# Phoenix_FC_shield.net
KiCad netlist of a schematic drawn in EAGLE
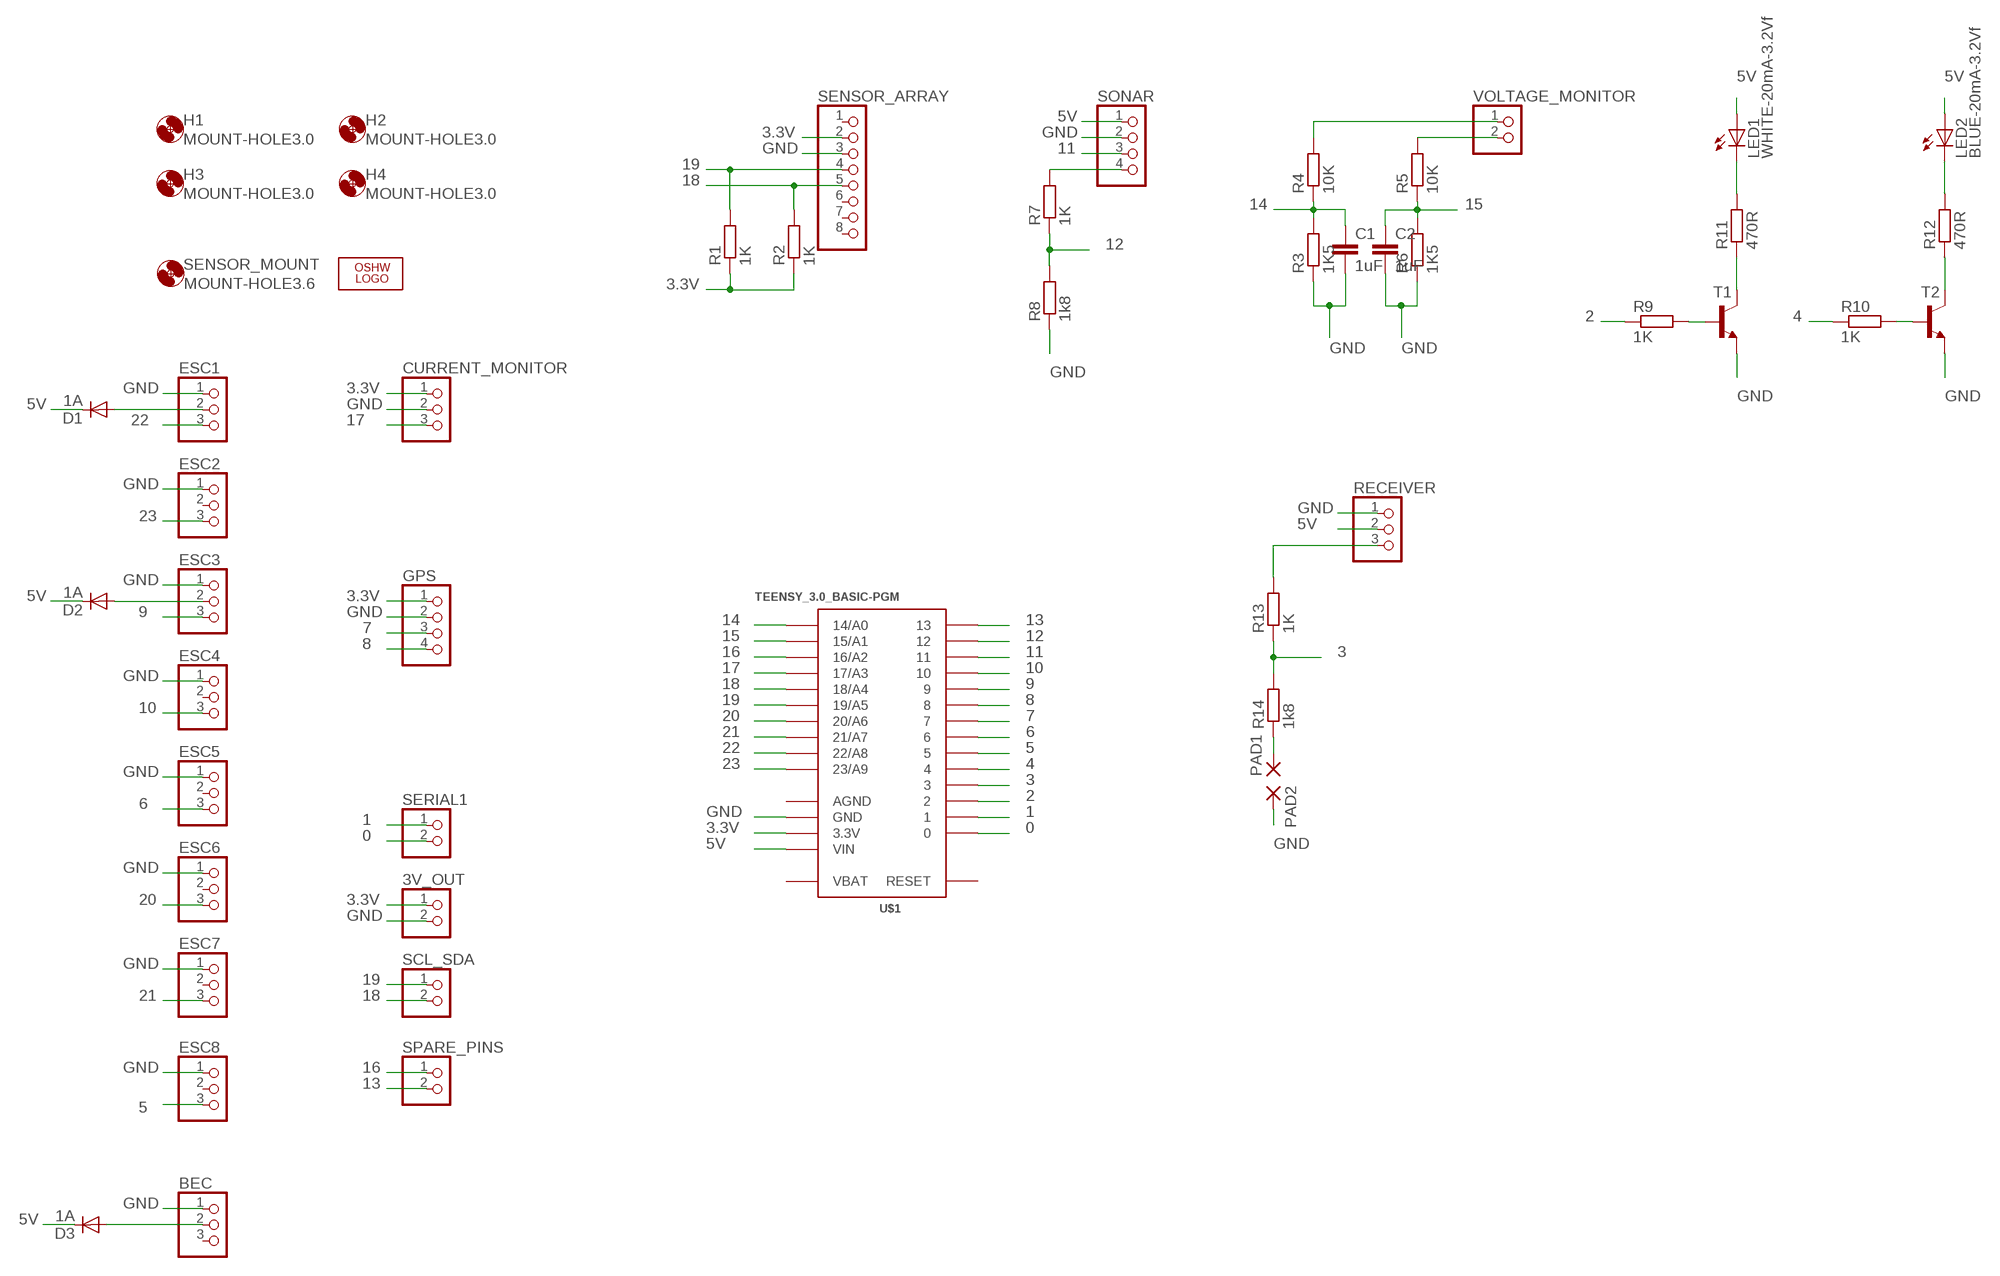
[diagram p0: schematic, sheet 1]

(export (version "E")
  (design (tool "Eeschema 10.0.6"))
  (components
    (comp (ref "3V_OUT")
      (value "PINHD-1X2")
      (footprint "eagle-import:1X02")
      (libsource (lib "eagle-import") (part "PINHD-1X2"))
    )
    (comp (ref "BEC")
      (value "PINHD-1X3")
      (footprint "eagle-import:1X03")
      (libsource (lib "eagle-import") (part "PINHD-1X3"))
    )
    (comp (ref "C1")
      (value "1uF")
      (footprint "eagle-import:C0805")
      (libsource (lib "eagle-import") (part "C-EUC0805"))
    )
    (comp (ref "C2")
      (value "1uF")
      (footprint "eagle-import:C0805")
      (libsource (lib "eagle-import") (part "C-EUC0805"))
    )
    (comp (ref "CURRENT_MONITOR")
      (value "PINHD-1X3")
      (footprint "eagle-import:1X03")
      (libsource (lib "eagle-import") (part "PINHD-1X3"))
    )
    (comp (ref "D1")
      (value "1A")
      (footprint "eagle-import:DO-214AC")
      (libsource (lib "eagle-import") (part "DIODE-DO-214AC"))
    )
    (comp (ref "D2")
      (value "1A")
      (footprint "eagle-import:DO-214AC")
      (libsource (lib "eagle-import") (part "DIODE-DO-214AC"))
    )
    (comp (ref "D3")
      (value "1A")
      (footprint "eagle-import:DO-214AC")
      (libsource (lib "eagle-import") (part "DIODE-DO-214AC"))
    )
    (comp (ref "ESC1")
      (value "PINHD-1X3")
      (footprint "eagle-import:1X03")
      (libsource (lib "eagle-import") (part "PINHD-1X3"))
    )
    (comp (ref "ESC2")
      (value "PINHD-1X3")
      (footprint "eagle-import:1X03")
      (libsource (lib "eagle-import") (part "PINHD-1X3"))
    )
    (comp (ref "ESC3")
      (value "PINHD-1X3")
      (footprint "eagle-import:1X03")
      (libsource (lib "eagle-import") (part "PINHD-1X3"))
    )
    (comp (ref "ESC4")
      (value "PINHD-1X3")
      (footprint "eagle-import:1X03")
      (libsource (lib "eagle-import") (part "PINHD-1X3"))
    )
    (comp (ref "ESC5")
      (value "PINHD-1X3")
      (footprint "eagle-import:1X03")
      (libsource (lib "eagle-import") (part "PINHD-1X3"))
    )
    (comp (ref "ESC6")
      (value "PINHD-1X3")
      (footprint "eagle-import:1X03")
      (libsource (lib "eagle-import") (part "PINHD-1X3"))
    )
    (comp (ref "ESC7")
      (value "PINHD-1X3")
      (footprint "eagle-import:1X03")
      (libsource (lib "eagle-import") (part "PINHD-1X3"))
    )
    (comp (ref "ESC8")
      (value "PINHD-1X3")
      (footprint "eagle-import:1X03")
      (libsource (lib "eagle-import") (part "PINHD-1X3"))
    )
    (comp (ref "GPS")
      (value "PINHD-1X4")
      (footprint "eagle-import:1X04")
      (libsource (lib "eagle-import") (part "PINHD-1X4"))
    )
    (comp (ref "H1")
      (value "MOUNT-HOLE3.0")
      (footprint "eagle-import:3,0")
      (libsource (lib "eagle-import") (part "MOUNT-HOLE3.0"))
    )
    (comp (ref "H2")
      (value "MOUNT-HOLE3.0")
      (footprint "eagle-import:3,0")
      (libsource (lib "eagle-import") (part "MOUNT-HOLE3.0"))
    )
    (comp (ref "H3")
      (value "MOUNT-HOLE3.0")
      (footprint "eagle-import:3,0")
      (libsource (lib "eagle-import") (part "MOUNT-HOLE3.0"))
    )
    (comp (ref "H4")
      (value "MOUNT-HOLE3.0")
      (footprint "eagle-import:3,0")
      (libsource (lib "eagle-import") (part "MOUNT-HOLE3.0"))
    )
    (comp (ref "LED1")
      (value "WHITE-20mA-3.2Vf")
      (footprint "eagle-import:CHIP-LED0805")
      (libsource (lib "eagle-import") (part "LEDCHIP-LED0805"))
    )
    (comp (ref "LED2")
      (value "BLUE-20mA-3.2Vf")
      (footprint "eagle-import:CHIP-LED0805")
      (libsource (lib "eagle-import") (part "LEDCHIP-LED0805"))
    )
    (comp (ref "LOGO1")
      (value "OSHW_LOGO_8MILX0200-NT")
      (footprint "eagle-import:OSHW_8X200_NOTEXT")
      (libsource (lib "eagle-import") (part "OSHW_LOGO_8MILX0200-NT"))
    )
    (comp (ref "PAD1")
      (value "WIREPADSMD1,27-254")
      (footprint "eagle-import:SMD1,27-2,54")
      (libsource (lib "eagle-import") (part "WIREPADSMD1,27-254"))
    )
    (comp (ref "PAD2")
      (value "WIREPADSMD1,27-254")
      (footprint "eagle-import:SMD1,27-2,54")
      (libsource (lib "eagle-import") (part "WIREPADSMD1,27-254"))
    )
    (comp (ref "R1")
      (value "1K")
      (footprint "eagle-import:R0805")
      (libsource (lib "eagle-import") (part "R-EU_R0805"))
    )
    (comp (ref "R2")
      (value "1K")
      (footprint "eagle-import:R0805")
      (libsource (lib "eagle-import") (part "R-EU_R0805"))
    )
    (comp (ref "R3")
      (value "1K5")
      (footprint "eagle-import:R0805")
      (libsource (lib "eagle-import") (part "R-EU_R0805"))
    )
    (comp (ref "R4")
      (value "10K")
      (footprint "eagle-import:R0805")
      (libsource (lib "eagle-import") (part "R-EU_R0805"))
    )
    (comp (ref "R5")
      (value "10K")
      (footprint "eagle-import:R0805")
      (libsource (lib "eagle-import") (part "R-EU_R0805"))
    )
    (comp (ref "R6")
      (value "1K5")
      (footprint "eagle-import:R0805")
      (libsource (lib "eagle-import") (part "R-EU_R0805"))
    )
    (comp (ref "R7")
      (value "1K")
      (footprint "eagle-import:R0805")
      (libsource (lib "eagle-import") (part "R-EU_R0805"))
    )
    (comp (ref "R8")
      (value "1k8")
      (footprint "eagle-import:R0805")
      (libsource (lib "eagle-import") (part "R-EU_R0805"))
    )
    (comp (ref "R9")
      (value "1K")
      (footprint "eagle-import:R0805")
      (libsource (lib "eagle-import") (part "R-EU_R0805"))
    )
    (comp (ref "R10")
      (value "1K")
      (footprint "eagle-import:R0805")
      (libsource (lib "eagle-import") (part "R-EU_R0805"))
    )
    (comp (ref "R11")
      (value "470R")
      (footprint "eagle-import:R0805")
      (libsource (lib "eagle-import") (part "R-EU_R0805"))
    )
    (comp (ref "R12")
      (value "470R")
      (footprint "eagle-import:R0805")
      (libsource (lib "eagle-import") (part "R-EU_R0805"))
    )
    (comp (ref "R13")
      (value "1K")
      (footprint "eagle-import:R0805")
      (libsource (lib "eagle-import") (part "R-EU_R0805"))
    )
    (comp (ref "R14")
      (value "1k8")
      (footprint "eagle-import:R0805")
      (libsource (lib "eagle-import") (part "R-EU_R0805"))
    )
    (comp (ref "RECEIVER")
      (value "PINHD-1X3")
      (footprint "eagle-import:1X03")
      (libsource (lib "eagle-import") (part "PINHD-1X3"))
    )
    (comp (ref "SCL_SDA")
      (value "PINHD-1X2")
      (footprint "eagle-import:1X02")
      (libsource (lib "eagle-import") (part "PINHD-1X2"))
    )
    (comp (ref "SENSOR_ARRAY")
      (value "PINHD-1X8")
      (footprint "eagle-import:1X08")
      (libsource (lib "eagle-import") (part "PINHD-1X8"))
    )
    (comp (ref "SENSOR_MOUNT")
      (value "MOUNT-HOLE3.6")
      (footprint "eagle-import:3,6")
      (libsource (lib "eagle-import") (part "MOUNT-HOLE3.6"))
    )
    (comp (ref "SERIAL1")
      (value "PINHD-1X2")
      (footprint "eagle-import:1X02")
      (libsource (lib "eagle-import") (part "PINHD-1X2"))
    )
    (comp (ref "SONAR")
      (value "PINHD-1X4")
      (footprint "eagle-import:1X04")
      (libsource (lib "eagle-import") (part "PINHD-1X4"))
    )
    (comp (ref "SPARE_PINS")
      (value "PINHD-1X2")
      (footprint "eagle-import:1X02")
      (libsource (lib "eagle-import") (part "PINHD-1X2"))
    )
    (comp (ref "T1")
      (value "BC817-40SMD")
      (footprint "eagle-import:SOT23-BEC")
      (libsource (lib "eagle-import") (part "BC817SMD-40"))
    )
    (comp (ref "T2")
      (value "BC817-40SMD")
      (footprint "eagle-import:SOT23-BEC")
      (libsource (lib "eagle-import") (part "BC817SMD-40"))
    )
    (comp (ref "U$1")
      (value "TEENSY_3.0_BASIC-PGM")
      (footprint "eagle-import:TEENSY_3.0_BASIC-PGM")
      (libsource (lib "eagle-import") (part "TEENSY_3.0_BASIC-PGM"))
    )
    (comp (ref "VOLTAGE_MONITOR")
      (value "PINHD-1X2")
      (footprint "eagle-import:1X02")
      (libsource (lib "eagle-import") (part "PINHD-1X2"))
    )
  )
  (nets
    (net (code "1") (name "/0") (class "Default")
      (node (ref "SERIAL1") (pin "2") (pinfunction "2_2") (pintype "passive"))
      (node (ref "U$1") (pin "0") (pinfunction "0_0") (pintype "bidirectional"))
    )
    (net (code "2") (name "/1") (class "Default")
      (node (ref "SERIAL1") (pin "1") (pinfunction "1_1") (pintype "passive"))
      (node (ref "U$1") (pin "1") (pinfunction "1_1") (pintype "bidirectional"))
    )
    (net (code "3") (name "/2") (class "Default")
      (node (ref "R9") (pin "1") (pinfunction "1_1") (pintype "passive"))
      (node (ref "U$1") (pin "2") (pinfunction "2_2") (pintype "bidirectional"))
    )
    (net (code "4") (name "/3") (class "Default")
      (node (ref "R13") (pin "1") (pinfunction "1_1") (pintype "passive"))
      (node (ref "R14") (pin "2") (pinfunction "2_2") (pintype "passive"))
      (node (ref "U$1") (pin "3") (pinfunction "3_3") (pintype "bidirectional"))
    )
    (net (code "5") (name "/3.3V") (class "Default")
      (node (ref "3V_OUT") (pin "1") (pinfunction "1_1") (pintype "passive"))
      (node (ref "CURRENT_MONITOR") (pin "1") (pinfunction "1_1") (pintype "passive"))
      (node (ref "GPS") (pin "1") (pinfunction "1_1") (pintype "passive"))
      (node (ref "R1") (pin "1") (pinfunction "1_1") (pintype "passive"))
      (node (ref "R2") (pin "1") (pinfunction "1_1") (pintype "passive"))
      (node (ref "SENSOR_ARRAY") (pin "2") (pinfunction "2_2") (pintype "passive"))
      (node (ref "U$1") (pin "3.3V") (pinfunction "3.3V_3.3V") (pintype "power_in"))
      (node (ref "U$1") (pin "3.3V1") (pinfunction "3.3V_3.3V1") (pintype "power_in"))
    )
    (net (code "6") (name "/4") (class "Default")
      (node (ref "R10") (pin "1") (pinfunction "1_1") (pintype "passive"))
      (node (ref "U$1") (pin "4") (pinfunction "4_4") (pintype "bidirectional"))
    )
    (net (code "7") (name "/5") (class "Default")
      (node (ref "ESC8") (pin "3") (pinfunction "3_3") (pintype "passive"))
      (node (ref "U$1") (pin "5") (pinfunction "5_5") (pintype "bidirectional"))
    )
    (net (code "8") (name "/5V") (class "Default")
      (node (ref "D1") (pin "C") (pinfunction "C_C") (pintype "passive"))
      (node (ref "D2") (pin "C") (pinfunction "C_C") (pintype "passive"))
      (node (ref "D3") (pin "C") (pinfunction "C_C") (pintype "passive"))
      (node (ref "LED1") (pin "A") (pinfunction "A_A") (pintype "passive"))
      (node (ref "LED2") (pin "A") (pinfunction "A_A") (pintype "passive"))
      (node (ref "RECEIVER") (pin "2") (pinfunction "2_2") (pintype "passive"))
      (node (ref "SONAR") (pin "1") (pinfunction "1_1") (pintype "passive"))
      (node (ref "U$1") (pin "VIN") (pinfunction "VIN_VIN") (pintype "power_in"))
    )
    (net (code "9") (name "/6") (class "Default")
      (node (ref "ESC5") (pin "3") (pinfunction "3_3") (pintype "passive"))
      (node (ref "U$1") (pin "6") (pinfunction "6_6") (pintype "bidirectional"))
    )
    (net (code "10") (name "/7") (class "Default")
      (node (ref "GPS") (pin "3") (pinfunction "3_3") (pintype "passive"))
      (node (ref "U$1") (pin "7") (pinfunction "7_7") (pintype "bidirectional"))
    )
    (net (code "11") (name "/8") (class "Default")
      (node (ref "GPS") (pin "4") (pinfunction "4_4") (pintype "passive"))
      (node (ref "U$1") (pin "8") (pinfunction "8_8") (pintype "bidirectional"))
    )
    (net (code "12") (name "/9") (class "Default")
      (node (ref "ESC3") (pin "3") (pinfunction "3_3") (pintype "passive"))
      (node (ref "U$1") (pin "9") (pinfunction "9_9") (pintype "bidirectional"))
    )
    (net (code "13") (name "/10") (class "Default")
      (node (ref "ESC4") (pin "3") (pinfunction "3_3") (pintype "passive"))
      (node (ref "U$1") (pin "10") (pinfunction "10_10") (pintype "bidirectional"))
    )
    (net (code "14") (name "/11") (class "Default")
      (node (ref "SONAR") (pin "3") (pinfunction "3_3") (pintype "passive"))
      (node (ref "U$1") (pin "11") (pinfunction "11_11") (pintype "bidirectional"))
    )
    (net (code "15") (name "/12") (class "Default")
      (node (ref "R7") (pin "1") (pinfunction "1_1") (pintype "passive"))
      (node (ref "R8") (pin "2") (pinfunction "2_2") (pintype "passive"))
      (node (ref "U$1") (pin "12") (pinfunction "12_12") (pintype "bidirectional"))
    )
    (net (code "16") (name "/13") (class "Default")
      (node (ref "SPARE_PINS") (pin "2") (pinfunction "2_2") (pintype "passive"))
      (node (ref "U$1") (pin "13") (pinfunction "13_13") (pintype "bidirectional"))
    )
    (net (code "17") (name "/14") (class "Default")
      (node (ref "C1") (pin "1") (pinfunction "1_1") (pintype "passive"))
      (node (ref "R3") (pin "2") (pinfunction "2_2") (pintype "passive"))
      (node (ref "R4") (pin "1") (pinfunction "1_1") (pintype "passive"))
      (node (ref "U$1") (pin "14/A0") (pinfunction "14/A0_14/A0") (pintype "bidirectional"))
    )
    (net (code "18") (name "/15") (class "Default")
      (node (ref "C2") (pin "1") (pinfunction "1_1") (pintype "passive"))
      (node (ref "R5") (pin "1") (pinfunction "1_1") (pintype "passive"))
      (node (ref "R6") (pin "2") (pinfunction "2_2") (pintype "passive"))
      (node (ref "U$1") (pin "15/A1") (pinfunction "15/A1_15/A1") (pintype "bidirectional"))
    )
    (net (code "19") (name "/16") (class "Default")
      (node (ref "SPARE_PINS") (pin "1") (pinfunction "1_1") (pintype "passive"))
      (node (ref "U$1") (pin "16/A2") (pinfunction "16/A2_16/A2") (pintype "bidirectional"))
    )
    (net (code "20") (name "/17") (class "Default")
      (node (ref "CURRENT_MONITOR") (pin "3") (pinfunction "3_3") (pintype "passive"))
      (node (ref "U$1") (pin "17/A3") (pinfunction "17/A3_17/A3") (pintype "bidirectional"))
    )
    (net (code "21") (name "/18") (class "Default")
      (node (ref "R2") (pin "2") (pinfunction "2_2") (pintype "passive"))
      (node (ref "SCL_SDA") (pin "2") (pinfunction "2_2") (pintype "passive"))
      (node (ref "SENSOR_ARRAY") (pin "5") (pinfunction "5_5") (pintype "passive"))
      (node (ref "U$1") (pin "18/A4") (pinfunction "18/A4_18/A4") (pintype "bidirectional"))
    )
    (net (code "22") (name "/19") (class "Default")
      (node (ref "R1") (pin "2") (pinfunction "2_2") (pintype "passive"))
      (node (ref "SCL_SDA") (pin "1") (pinfunction "1_1") (pintype "passive"))
      (node (ref "SENSOR_ARRAY") (pin "4") (pinfunction "4_4") (pintype "passive"))
      (node (ref "U$1") (pin "19/A5") (pinfunction "19/A5_19/A5") (pintype "bidirectional"))
    )
    (net (code "23") (name "/20") (class "Default")
      (node (ref "ESC6") (pin "3") (pinfunction "3_3") (pintype "passive"))
      (node (ref "U$1") (pin "20/A6") (pinfunction "20/A6_20/A6") (pintype "bidirectional"))
    )
    (net (code "24") (name "/21") (class "Default")
      (node (ref "ESC7") (pin "3") (pinfunction "3_3") (pintype "passive"))
      (node (ref "U$1") (pin "21/A7") (pinfunction "21/A7_21/A7") (pintype "bidirectional"))
    )
    (net (code "25") (name "/22") (class "Default")
      (node (ref "ESC1") (pin "3") (pinfunction "3_3") (pintype "passive"))
      (node (ref "U$1") (pin "22/A8") (pinfunction "22/A8_22/A8") (pintype "bidirectional"))
    )
    (net (code "26") (name "/23") (class "Default")
      (node (ref "ESC2") (pin "3") (pinfunction "3_3") (pintype "passive"))
      (node (ref "U$1") (pin "23/A9") (pinfunction "23/A9_23/A9") (pintype "bidirectional"))
    )
    (net (code "27") (name "/AGND") (class "Default")
      (node (ref "U$1") (pin "AGND") (pinfunction "AGND_AGND") (pintype "power_in"))
    )
    (net (code "28") (name "/GND") (class "Default")
      (node (ref "3V_OUT") (pin "2") (pinfunction "2_2") (pintype "passive"))
      (node (ref "BEC") (pin "1") (pinfunction "1_1") (pintype "passive"))
      (node (ref "C1") (pin "2") (pinfunction "2_2") (pintype "passive"))
      (node (ref "C2") (pin "2") (pinfunction "2_2") (pintype "passive"))
      (node (ref "CURRENT_MONITOR") (pin "2") (pinfunction "2_2") (pintype "passive"))
      (node (ref "ESC1") (pin "1") (pinfunction "1_1") (pintype "passive"))
      (node (ref "ESC2") (pin "1") (pinfunction "1_1") (pintype "passive"))
      (node (ref "ESC3") (pin "1") (pinfunction "1_1") (pintype "passive"))
      (node (ref "ESC4") (pin "1") (pinfunction "1_1") (pintype "passive"))
      (node (ref "ESC5") (pin "1") (pinfunction "1_1") (pintype "passive"))
      (node (ref "ESC6") (pin "1") (pinfunction "1_1") (pintype "passive"))
      (node (ref "ESC7") (pin "1") (pinfunction "1_1") (pintype "passive"))
      (node (ref "ESC8") (pin "1") (pinfunction "1_1") (pintype "passive"))
      (node (ref "GPS") (pin "2") (pinfunction "2_2") (pintype "passive"))
      (node (ref "PAD2") (pin "1") (pinfunction "P_1") (pintype "passive"))
      (node (ref "R3") (pin "1") (pinfunction "1_1") (pintype "passive"))
      (node (ref "R6") (pin "1") (pinfunction "1_1") (pintype "passive"))
      (node (ref "R8") (pin "1") (pinfunction "1_1") (pintype "passive"))
      (node (ref "RECEIVER") (pin "1") (pinfunction "1_1") (pintype "passive"))
      (node (ref "SENSOR_ARRAY") (pin "3") (pinfunction "3_3") (pintype "passive"))
      (node (ref "SONAR") (pin "2") (pinfunction "2_2") (pintype "passive"))
      (node (ref "T1") (pin "E") (pinfunction "E_E") (pintype "passive"))
      (node (ref "T2") (pin "E") (pinfunction "E_E") (pintype "passive"))
      (node (ref "U$1") (pin "GND") (pinfunction "GND_GND") (pintype "power_in"))
      (node (ref "U$1") (pin "GND1") (pinfunction "GND_GND1") (pintype "power_in"))
    )
    (net (code "29") (name "/VBAT") (class "Default")
      (node (ref "U$1") (pin "VBAT") (pinfunction "VBAT_VBAT") (pintype "power_in"))
    )
    (net (code "30") (name "Net-(BEC-Pad2)") (class "Default")
      (node (ref "BEC") (pin "2") (pinfunction "2_2") (pintype "passive"))
      (node (ref "D3") (pin "A") (pinfunction "A_A") (pintype "passive"))
    )
    (net (code "31") (name "Net-(D1-PadA)") (class "Default")
      (node (ref "D1") (pin "A") (pinfunction "A_A") (pintype "passive"))
      (node (ref "ESC1") (pin "2") (pinfunction "2_2") (pintype "passive"))
    )
    (net (code "32") (name "Net-(D2-PadA)") (class "Default")
      (node (ref "D2") (pin "A") (pinfunction "A_A") (pintype "passive"))
      (node (ref "ESC3") (pin "2") (pinfunction "2_2") (pintype "passive"))
    )
    (net (code "33") (name "Net-(LED1-PadC)") (class "Default")
      (node (ref "LED1") (pin "C") (pinfunction "C_C") (pintype "passive"))
      (node (ref "R11") (pin "2") (pinfunction "2_2") (pintype "passive"))
    )
    (net (code "34") (name "Net-(LED2-PadC)") (class "Default")
      (node (ref "LED2") (pin "C") (pinfunction "C_C") (pintype "passive"))
      (node (ref "R12") (pin "2") (pinfunction "2_2") (pintype "passive"))
    )
    (net (code "35") (name "Net-(PAD1-P)") (class "Default")
      (node (ref "PAD1") (pin "1") (pinfunction "P_1") (pintype "passive"))
      (node (ref "R14") (pin "1") (pinfunction "1_1") (pintype "passive"))
    )
    (net (code "36") (name "Net-(R4-Pad2)") (class "Default")
      (node (ref "R4") (pin "2") (pinfunction "2_2") (pintype "passive"))
      (node (ref "VOLTAGE_MONITOR") (pin "1") (pinfunction "1_1") (pintype "passive"))
    )
    (net (code "37") (name "Net-(R5-Pad2)") (class "Default")
      (node (ref "R5") (pin "2") (pinfunction "2_2") (pintype "passive"))
      (node (ref "VOLTAGE_MONITOR") (pin "2") (pinfunction "2_2") (pintype "passive"))
    )
    (net (code "38") (name "Net-(R7-Pad2)") (class "Default")
      (node (ref "R7") (pin "2") (pinfunction "2_2") (pintype "passive"))
      (node (ref "SONAR") (pin "4") (pinfunction "4_4") (pintype "passive"))
    )
    (net (code "39") (name "Net-(R9-Pad2)") (class "Default")
      (node (ref "R9") (pin "2") (pinfunction "2_2") (pintype "passive"))
      (node (ref "T1") (pin "B") (pinfunction "B_B") (pintype "passive"))
    )
    (net (code "40") (name "Net-(R10-Pad2)") (class "Default")
      (node (ref "R10") (pin "2") (pinfunction "2_2") (pintype "passive"))
      (node (ref "T2") (pin "B") (pinfunction "B_B") (pintype "passive"))
    )
    (net (code "41") (name "Net-(R11-Pad1)") (class "Default")
      (node (ref "R11") (pin "1") (pinfunction "1_1") (pintype "passive"))
      (node (ref "T1") (pin "C") (pinfunction "C_C") (pintype "passive"))
    )
    (net (code "42") (name "Net-(R12-Pad1)") (class "Default")
      (node (ref "R12") (pin "1") (pinfunction "1_1") (pintype "passive"))
      (node (ref "T2") (pin "C") (pinfunction "C_C") (pintype "passive"))
    )
    (net (code "43") (name "Net-(R13-Pad2)") (class "Default")
      (node (ref "R13") (pin "2") (pinfunction "2_2") (pintype "passive"))
      (node (ref "RECEIVER") (pin "3") (pinfunction "3_3") (pintype "passive"))
    )
    (net (code "44") (name "unconnected-(BEC-Pad3)") (class "Default")
      (node (ref "BEC") (pin "3") (pinfunction "3_3") (pintype "passive"))
    )
    (net (code "45") (name "unconnected-(ESC2-Pad2)") (class "Default")
      (node (ref "ESC2") (pin "2") (pinfunction "2_2") (pintype "passive"))
    )
    (net (code "46") (name "unconnected-(ESC4-Pad2)") (class "Default")
      (node (ref "ESC4") (pin "2") (pinfunction "2_2") (pintype "passive"))
    )
    (net (code "47") (name "unconnected-(ESC5-Pad2)") (class "Default")
      (node (ref "ESC5") (pin "2") (pinfunction "2_2") (pintype "passive"))
    )
    (net (code "48") (name "unconnected-(ESC6-Pad2)") (class "Default")
      (node (ref "ESC6") (pin "2") (pinfunction "2_2") (pintype "passive"))
    )
    (net (code "49") (name "unconnected-(ESC7-Pad2)") (class "Default")
      (node (ref "ESC7") (pin "2") (pinfunction "2_2") (pintype "passive"))
    )
    (net (code "50") (name "unconnected-(ESC8-Pad2)") (class "Default")
      (node (ref "ESC8") (pin "2") (pinfunction "2_2") (pintype "passive"))
    )
    (net (code "51") (name "unconnected-(SENSOR_ARRAY-Pad1)") (class "Default")
      (node (ref "SENSOR_ARRAY") (pin "1") (pinfunction "1_1") (pintype "passive"))
    )
    (net (code "52") (name "unconnected-(SENSOR_ARRAY-Pad6)") (class "Default")
      (node (ref "SENSOR_ARRAY") (pin "6") (pinfunction "6_6") (pintype "passive"))
    )
    (net (code "53") (name "unconnected-(SENSOR_ARRAY-Pad7)") (class "Default")
      (node (ref "SENSOR_ARRAY") (pin "7") (pinfunction "7_7") (pintype "passive"))
    )
    (net (code "54") (name "unconnected-(SENSOR_ARRAY-Pad8)") (class "Default")
      (node (ref "SENSOR_ARRAY") (pin "8") (pinfunction "8_8") (pintype "passive"))
    )
    (net (code "55") (name "unconnected-(U$1-PadRESET)") (class "Default")
      (node (ref "U$1") (pin "RESET") (pinfunction "RESET_RESET") (pintype "bidirectional"))
    )
  )
)
